# LED_connections.net
KiCad netlist of a schematic drawn in EAGLE
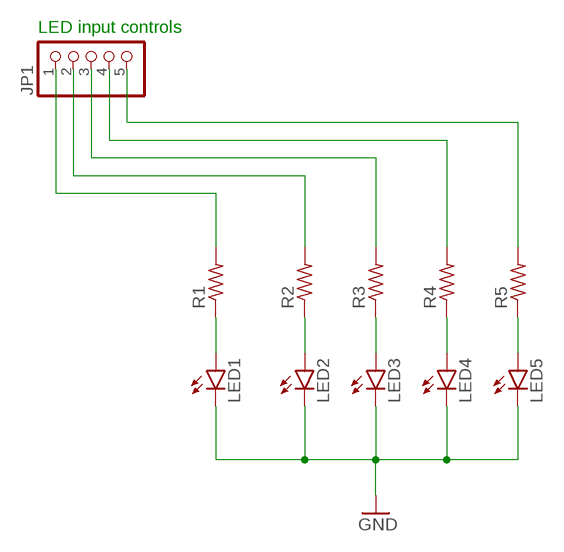
[diagram p0: schematic, sheet 1]

(export (version "E")
  (design (tool "Eeschema 10.0.6"))
  (components
    (comp (ref "JP1")
      (value "PINHD-1X5")
      (footprint "eagle-import:1X05")
      (libsource (lib "eagle-import") (part "PINHD-1X5"))
    )
    (comp (ref "LED1")
      (value "LED5MM")
      (footprint "eagle-import:LED5MM")
      (libsource (lib "eagle-import") (part "LED5MM"))
    )
    (comp (ref "LED2")
      (value "LED5MM")
      (footprint "eagle-import:LED5MM")
      (libsource (lib "eagle-import") (part "LED5MM"))
    )
    (comp (ref "LED3")
      (value "LED5MM")
      (footprint "eagle-import:LED5MM")
      (libsource (lib "eagle-import") (part "LED5MM"))
    )
    (comp (ref "LED4")
      (value "LED5MM")
      (footprint "eagle-import:LED5MM")
      (libsource (lib "eagle-import") (part "LED5MM"))
    )
    (comp (ref "LED5")
      (value "LED5MM")
      (footprint "eagle-import:LED5MM")
      (libsource (lib "eagle-import") (part "LED5MM"))
    )
    (comp (ref "R1")
      (value "R-US_0207/7")
      (footprint "eagle-import:0207_7")
      (libsource (lib "eagle-import") (part "R-US_0207/7"))
    )
    (comp (ref "R2")
      (value "R-US_0207/7")
      (footprint "eagle-import:0207_7")
      (libsource (lib "eagle-import") (part "R-US_0207/7"))
    )
    (comp (ref "R3")
      (value "R-US_0207/7")
      (footprint "eagle-import:0207_7")
      (libsource (lib "eagle-import") (part "R-US_0207/7"))
    )
    (comp (ref "R4")
      (value "R-US_0207/7")
      (footprint "eagle-import:0207_7")
      (libsource (lib "eagle-import") (part "R-US_0207/7"))
    )
    (comp (ref "R5")
      (value "R-US_0207/7")
      (footprint "eagle-import:0207_7")
      (libsource (lib "eagle-import") (part "R-US_0207/7"))
    )
  )
  (nets
    (net (code "1") (name "GND") (class "Default")
      (node (ref "LED1") (pin "K") (pinfunction "C_K") (pintype "passive"))
      (node (ref "LED2") (pin "K") (pinfunction "C_K") (pintype "passive"))
      (node (ref "LED3") (pin "K") (pinfunction "C_K") (pintype "passive"))
      (node (ref "LED4") (pin "K") (pinfunction "C_K") (pintype "passive"))
      (node (ref "LED5") (pin "K") (pinfunction "C_K") (pintype "passive"))
    )
    (net (code "2") (name "Net-(JP1-Pad1)") (class "Default")
      (node (ref "JP1") (pin "1") (pinfunction "1_1") (pintype "passive"))
      (node (ref "R1") (pin "2") (pinfunction "2_2") (pintype "passive"))
    )
    (net (code "3") (name "Net-(JP1-Pad2)") (class "Default")
      (node (ref "JP1") (pin "2") (pinfunction "2_2") (pintype "passive"))
      (node (ref "R2") (pin "2") (pinfunction "2_2") (pintype "passive"))
    )
    (net (code "4") (name "Net-(JP1-Pad3)") (class "Default")
      (node (ref "JP1") (pin "3") (pinfunction "3_3") (pintype "passive"))
      (node (ref "R3") (pin "2") (pinfunction "2_2") (pintype "passive"))
    )
    (net (code "5") (name "Net-(JP1-Pad4)") (class "Default")
      (node (ref "JP1") (pin "4") (pinfunction "4_4") (pintype "passive"))
      (node (ref "R4") (pin "2") (pinfunction "2_2") (pintype "passive"))
    )
    (net (code "6") (name "Net-(JP1-Pad5)") (class "Default")
      (node (ref "JP1") (pin "5") (pinfunction "5_5") (pintype "passive"))
      (node (ref "R5") (pin "2") (pinfunction "2_2") (pintype "passive"))
    )
    (net (code "7") (name "Net-(LED1-PadA)") (class "Default")
      (node (ref "LED1") (pin "A") (pinfunction "A_A") (pintype "passive"))
      (node (ref "R1") (pin "1") (pinfunction "1_1") (pintype "passive"))
    )
    (net (code "8") (name "Net-(LED2-PadA)") (class "Default")
      (node (ref "LED2") (pin "A") (pinfunction "A_A") (pintype "passive"))
      (node (ref "R2") (pin "1") (pinfunction "1_1") (pintype "passive"))
    )
    (net (code "9") (name "Net-(LED3-PadA)") (class "Default")
      (node (ref "LED3") (pin "A") (pinfunction "A_A") (pintype "passive"))
      (node (ref "R3") (pin "1") (pinfunction "1_1") (pintype "passive"))
    )
    (net (code "10") (name "Net-(LED4-PadA)") (class "Default")
      (node (ref "LED4") (pin "A") (pinfunction "A_A") (pintype "passive"))
      (node (ref "R4") (pin "1") (pinfunction "1_1") (pintype "passive"))
    )
    (net (code "11") (name "Net-(LED5-PadA)") (class "Default")
      (node (ref "LED5") (pin "A") (pinfunction "A_A") (pintype "passive"))
      (node (ref "R5") (pin "1") (pinfunction "1_1") (pintype "passive"))
    )
  )
)
